# Top.net
KiCad netlist of a schematic drawn in Altium Designer
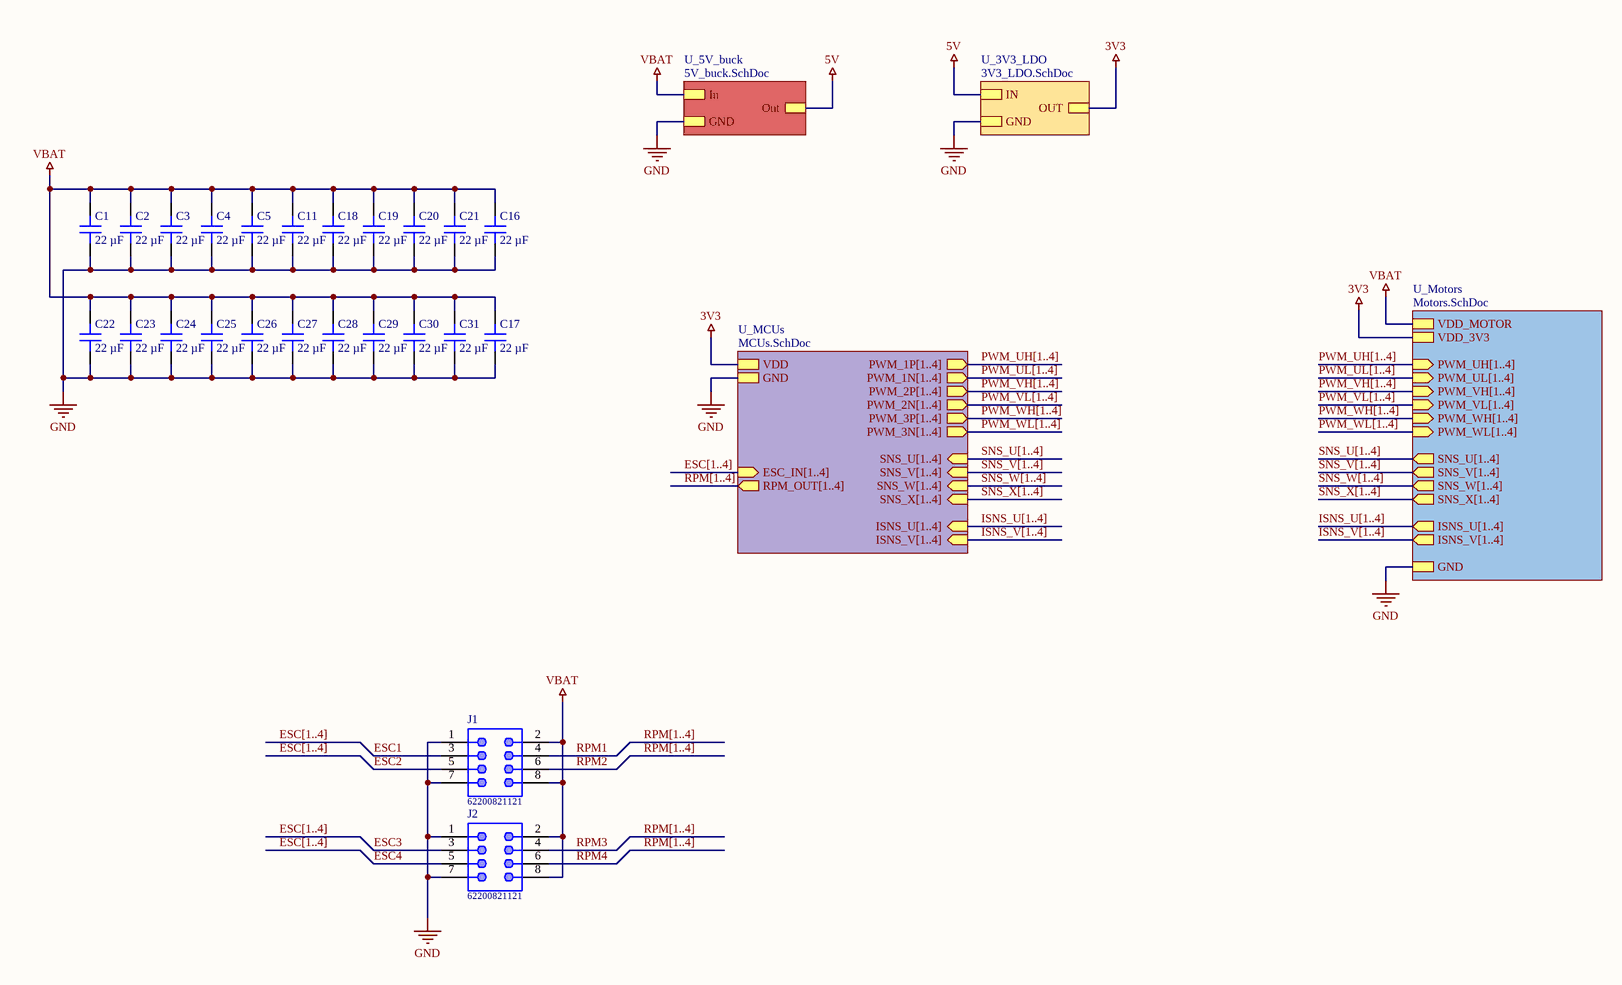
[diagram p0: Top.SchDoc]

(export (version "E")
  (design (tool "Eeschema 10.0.6"))
  (components
    (comp (ref "C1")
      (value "22 µF")
      (footprint "CAP 0805_2012")
      (description "CAP CER 22UF 25V X5R 0805")
      (fields (field (name "PART NUMBER") "CC0805MKX5R8BB226") (field (name "MANUFACTURER") "Yageo"))
      (libsource (lib "Celestial Altium Library - altium_library") (part "Capacitor"))
    )
    (comp (ref "C2")
      (value "22 µF")
      (footprint "CAP 0805_2012")
      (description "CAP CER 22UF 25V X5R 0805")
      (fields (field (name "PART NUMBER") "CC0805MKX5R8BB226") (field (name "MANUFACTURER") "Yageo"))
      (libsource (lib "Celestial Altium Library - altium_library") (part "Capacitor"))
    )
    (comp (ref "C3")
      (value "22 µF")
      (footprint "CAP 0805_2012")
      (description "CAP CER 22UF 25V X5R 0805")
      (fields (field (name "PART NUMBER") "CC0805MKX5R8BB226") (field (name "MANUFACTURER") "Yageo"))
      (libsource (lib "Celestial Altium Library - altium_library") (part "Capacitor"))
    )
    (comp (ref "C4")
      (value "22 µF")
      (footprint "CAP 0805_2012")
      (description "CAP CER 22UF 25V X5R 0805")
      (fields (field (name "PART NUMBER") "CC0805MKX5R8BB226") (field (name "MANUFACTURER") "Yageo"))
      (libsource (lib "Celestial Altium Library - altium_library") (part "Capacitor"))
    )
    (comp (ref "C5")
      (value "22 µF")
      (footprint "CAP 0805_2012")
      (description "CAP CER 22UF 25V X5R 0805")
      (fields (field (name "PART NUMBER") "CC0805MKX5R8BB226") (field (name "MANUFACTURER") "Yageo"))
      (libsource (lib "Celestial Altium Library - altium_library") (part "Capacitor"))
    )
    (comp (ref "C11")
      (value "22 µF")
      (footprint "CAP 0805_2012")
      (description "CAP CER 22UF 25V X5R 0805")
      (fields (field (name "PART NUMBER") "CC0805MKX5R8BB226") (field (name "MANUFACTURER") "Yageo"))
      (libsource (lib "Celestial Altium Library - altium_library") (part "Capacitor"))
    )
    (comp (ref "C16")
      (value "22 µF")
      (footprint "CAP 0805_2012")
      (description "CAP CER 22UF 25V X5R 0805")
      (fields (field (name "PART NUMBER") "CC0805MKX5R8BB226") (field (name "MANUFACTURER") "Yageo"))
      (libsource (lib "Celestial Altium Library - altium_library") (part "Capacitor"))
    )
    (comp (ref "C17")
      (value "22 µF")
      (footprint "CAP 0805_2012")
      (description "CAP CER 22UF 25V X5R 0805")
      (fields (field (name "PART NUMBER") "CC0805MKX5R8BB226") (field (name "MANUFACTURER") "Yageo"))
      (libsource (lib "Celestial Altium Library - altium_library") (part "Capacitor"))
    )
    (comp (ref "C18")
      (value "22 µF")
      (footprint "CAP 0805_2012")
      (description "CAP CER 22UF 25V X5R 0805")
      (fields (field (name "PART NUMBER") "CC0805MKX5R8BB226") (field (name "MANUFACTURER") "Yageo"))
      (libsource (lib "Celestial Altium Library - altium_library") (part "Capacitor"))
    )
    (comp (ref "C19")
      (value "22 µF")
      (footprint "CAP 0805_2012")
      (description "CAP CER 22UF 25V X5R 0805")
      (fields (field (name "PART NUMBER") "CC0805MKX5R8BB226") (field (name "MANUFACTURER") "Yageo"))
      (libsource (lib "Celestial Altium Library - altium_library") (part "Capacitor"))
    )
    (comp (ref "C20")
      (value "22 µF")
      (footprint "CAP 0805_2012")
      (description "CAP CER 22UF 25V X5R 0805")
      (fields (field (name "PART NUMBER") "CC0805MKX5R8BB226") (field (name "MANUFACTURER") "Yageo"))
      (libsource (lib "Celestial Altium Library - altium_library") (part "Capacitor"))
    )
    (comp (ref "C21")
      (value "22 µF")
      (footprint "CAP 0805_2012")
      (description "CAP CER 22UF 25V X5R 0805")
      (fields (field (name "PART NUMBER") "CC0805MKX5R8BB226") (field (name "MANUFACTURER") "Yageo"))
      (libsource (lib "Celestial Altium Library - altium_library") (part "Capacitor"))
    )
    (comp (ref "C22")
      (value "22 µF")
      (footprint "CAP 0805_2012")
      (description "CAP CER 22UF 25V X5R 0805")
      (fields (field (name "PART NUMBER") "CC0805MKX5R8BB226") (field (name "MANUFACTURER") "Yageo"))
      (libsource (lib "Celestial Altium Library - altium_library") (part "Capacitor"))
    )
    (comp (ref "C23")
      (value "22 µF")
      (footprint "CAP 0805_2012")
      (description "CAP CER 22UF 25V X5R 0805")
      (fields (field (name "PART NUMBER") "CC0805MKX5R8BB226") (field (name "MANUFACTURER") "Yageo"))
      (libsource (lib "Celestial Altium Library - altium_library") (part "Capacitor"))
    )
    (comp (ref "C24")
      (value "22 µF")
      (footprint "CAP 0805_2012")
      (description "CAP CER 22UF 25V X5R 0805")
      (fields (field (name "PART NUMBER") "CC0805MKX5R8BB226") (field (name "MANUFACTURER") "Yageo"))
      (libsource (lib "Celestial Altium Library - altium_library") (part "Capacitor"))
    )
    (comp (ref "C25")
      (value "22 µF")
      (footprint "CAP 0805_2012")
      (description "CAP CER 22UF 25V X5R 0805")
      (fields (field (name "PART NUMBER") "CC0805MKX5R8BB226") (field (name "MANUFACTURER") "Yageo"))
      (libsource (lib "Celestial Altium Library - altium_library") (part "Capacitor"))
    )
    (comp (ref "C26")
      (value "22 µF")
      (footprint "CAP 0805_2012")
      (description "CAP CER 22UF 25V X5R 0805")
      (fields (field (name "PART NUMBER") "CC0805MKX5R8BB226") (field (name "MANUFACTURER") "Yageo"))
      (libsource (lib "Celestial Altium Library - altium_library") (part "Capacitor"))
    )
    (comp (ref "C27")
      (value "22 µF")
      (footprint "CAP 0805_2012")
      (description "CAP CER 22UF 25V X5R 0805")
      (fields (field (name "PART NUMBER") "CC0805MKX5R8BB226") (field (name "MANUFACTURER") "Yageo"))
      (libsource (lib "Celestial Altium Library - altium_library") (part "Capacitor"))
    )
    (comp (ref "C28")
      (value "22 µF")
      (footprint "CAP 0805_2012")
      (description "CAP CER 22UF 25V X5R 0805")
      (fields (field (name "PART NUMBER") "CC0805MKX5R8BB226") (field (name "MANUFACTURER") "Yageo"))
      (libsource (lib "Celestial Altium Library - altium_library") (part "Capacitor"))
    )
    (comp (ref "C29")
      (value "22 µF")
      (footprint "CAP 0805_2012")
      (description "CAP CER 22UF 25V X5R 0805")
      (fields (field (name "PART NUMBER") "CC0805MKX5R8BB226") (field (name "MANUFACTURER") "Yageo"))
      (libsource (lib "Celestial Altium Library - altium_library") (part "Capacitor"))
    )
    (comp (ref "C30")
      (value "22 µF")
      (footprint "CAP 0805_2012")
      (description "CAP CER 22UF 25V X5R 0805")
      (fields (field (name "PART NUMBER") "CC0805MKX5R8BB226") (field (name "MANUFACTURER") "Yageo"))
      (libsource (lib "Celestial Altium Library - altium_library") (part "Capacitor"))
    )
    (comp (ref "C31")
      (value "22 µF")
      (footprint "CAP 0805_2012")
      (description "CAP CER 22UF 25V X5R 0805")
      (fields (field (name "PART NUMBER") "CC0805MKX5R8BB226") (field (name "MANUFACTURER") "Yageo"))
      (libsource (lib "Celestial Altium Library - altium_library") (part "Capacitor"))
    )
    (comp (ref "J1")
      (value "62200821121")
      (footprint "62200821121")
      (description "WR-PHD Pin Header, THT, pitch 1.27mm, Dual Row, Vertical, 8p")
      (fields (field (name "MANUFACTURER") "Wurth Elektronik"))
      (libsource (lib "Altium_WR-PHD") (part "62200821121"))
    )
    (comp (ref "J2")
      (value "62200821121")
      (footprint "62200821121")
      (description "WR-PHD Pin Header, THT, pitch 1.27mm, Dual Row, Vertical, 8p")
      (fields (field (name "MANUFACTURER") "Wurth Elektronik"))
      (libsource (lib "Altium_WR-PHD") (part "62200821121"))
    )
  )
  (nets
    (net (code "49") (name "/ESC1") (class "Default")
      (node (ref "J1") (pin "3") (pinfunction "3_3") (pintype "passive"))
    )
    (net (code "50") (name "/ESC2") (class "Default")
      (node (ref "J1") (pin "5") (pinfunction "5_5") (pintype "passive"))
    )
    (net (code "51") (name "/ESC3") (class "Default")
      (node (ref "J2") (pin "3") (pinfunction "3_3") (pintype "passive"))
    )
    (net (code "52") (name "/ESC4") (class "Default")
      (node (ref "J2") (pin "5") (pinfunction "5_5") (pintype "passive"))
    )
    (net (code "62") (name "/RPM1") (class "Default")
      (node (ref "J1") (pin "4") (pinfunction "4_4") (pintype "passive"))
    )
    (net (code "63") (name "/RPM2") (class "Default")
      (node (ref "J1") (pin "6") (pinfunction "6_6") (pintype "passive"))
    )
    (net (code "64") (name "/RPM3") (class "Default")
      (node (ref "J2") (pin "4") (pinfunction "4_4") (pintype "passive"))
    )
    (net (code "65") (name "/RPM4") (class "Default")
      (node (ref "J2") (pin "6") (pinfunction "6_6") (pintype "passive"))
    )
    (net (code "73") (name "GND") (class "Default")
      (node (ref "C1") (pin "1") (pinfunction "1_1") (pintype "passive"))
      (node (ref "C11") (pin "1") (pinfunction "1_1") (pintype "passive"))
      (node (ref "C16") (pin "1") (pinfunction "1_1") (pintype "passive"))
      (node (ref "C17") (pin "1") (pinfunction "1_1") (pintype "passive"))
      (node (ref "C18") (pin "1") (pinfunction "1_1") (pintype "passive"))
      (node (ref "C19") (pin "1") (pinfunction "1_1") (pintype "passive"))
      (node (ref "C2") (pin "1") (pinfunction "1_1") (pintype "passive"))
      (node (ref "C20") (pin "1") (pinfunction "1_1") (pintype "passive"))
      (node (ref "C21") (pin "1") (pinfunction "1_1") (pintype "passive"))
      (node (ref "C22") (pin "1") (pinfunction "1_1") (pintype "passive"))
      (node (ref "C23") (pin "1") (pinfunction "1_1") (pintype "passive"))
      (node (ref "C24") (pin "1") (pinfunction "1_1") (pintype "passive"))
      (node (ref "C25") (pin "1") (pinfunction "1_1") (pintype "passive"))
      (node (ref "C26") (pin "1") (pinfunction "1_1") (pintype "passive"))
      (node (ref "C27") (pin "1") (pinfunction "1_1") (pintype "passive"))
      (node (ref "C28") (pin "1") (pinfunction "1_1") (pintype "passive"))
      (node (ref "C29") (pin "1") (pinfunction "1_1") (pintype "passive"))
      (node (ref "C3") (pin "1") (pinfunction "1_1") (pintype "passive"))
      (node (ref "C30") (pin "1") (pinfunction "1_1") (pintype "passive"))
      (node (ref "C31") (pin "1") (pinfunction "1_1") (pintype "passive"))
      (node (ref "C4") (pin "1") (pinfunction "1_1") (pintype "passive"))
      (node (ref "C5") (pin "1") (pinfunction "1_1") (pintype "passive"))
      (node (ref "J1") (pin "1") (pinfunction "1_1") (pintype "passive"))
      (node (ref "J1") (pin "7") (pinfunction "7_7") (pintype "passive"))
      (node (ref "J2") (pin "1") (pinfunction "1_1") (pintype "passive"))
      (node (ref "J2") (pin "7") (pinfunction "7_7") (pintype "passive"))
    )
    (net (code "74") (name "VBAT") (class "Default")
      (node (ref "C1") (pin "2") (pinfunction "2_2") (pintype "passive"))
      (node (ref "C11") (pin "2") (pinfunction "2_2") (pintype "passive"))
      (node (ref "C16") (pin "2") (pinfunction "2_2") (pintype "passive"))
      (node (ref "C17") (pin "2") (pinfunction "2_2") (pintype "passive"))
      (node (ref "C18") (pin "2") (pinfunction "2_2") (pintype "passive"))
      (node (ref "C19") (pin "2") (pinfunction "2_2") (pintype "passive"))
      (node (ref "C2") (pin "2") (pinfunction "2_2") (pintype "passive"))
      (node (ref "C20") (pin "2") (pinfunction "2_2") (pintype "passive"))
      (node (ref "C21") (pin "2") (pinfunction "2_2") (pintype "passive"))
      (node (ref "C22") (pin "2") (pinfunction "2_2") (pintype "passive"))
      (node (ref "C23") (pin "2") (pinfunction "2_2") (pintype "passive"))
      (node (ref "C24") (pin "2") (pinfunction "2_2") (pintype "passive"))
      (node (ref "C25") (pin "2") (pinfunction "2_2") (pintype "passive"))
      (node (ref "C26") (pin "2") (pinfunction "2_2") (pintype "passive"))
      (node (ref "C27") (pin "2") (pinfunction "2_2") (pintype "passive"))
      (node (ref "C28") (pin "2") (pinfunction "2_2") (pintype "passive"))
      (node (ref "C29") (pin "2") (pinfunction "2_2") (pintype "passive"))
      (node (ref "C3") (pin "2") (pinfunction "2_2") (pintype "passive"))
      (node (ref "C30") (pin "2") (pinfunction "2_2") (pintype "passive"))
      (node (ref "C31") (pin "2") (pinfunction "2_2") (pintype "passive"))
      (node (ref "C4") (pin "2") (pinfunction "2_2") (pintype "passive"))
      (node (ref "C5") (pin "2") (pinfunction "2_2") (pintype "passive"))
      (node (ref "J1") (pin "2") (pinfunction "2_2") (pintype "passive"))
      (node (ref "J1") (pin "8") (pinfunction "8_8") (pintype "passive"))
      (node (ref "J2") (pin "2") (pinfunction "2_2") (pintype "passive"))
      (node (ref "J2") (pin "8") (pinfunction "8_8") (pintype "passive"))
    )
  )
)
